# HE280PCB.net
KiCad netlist of a schematic drawn in Altium Designer
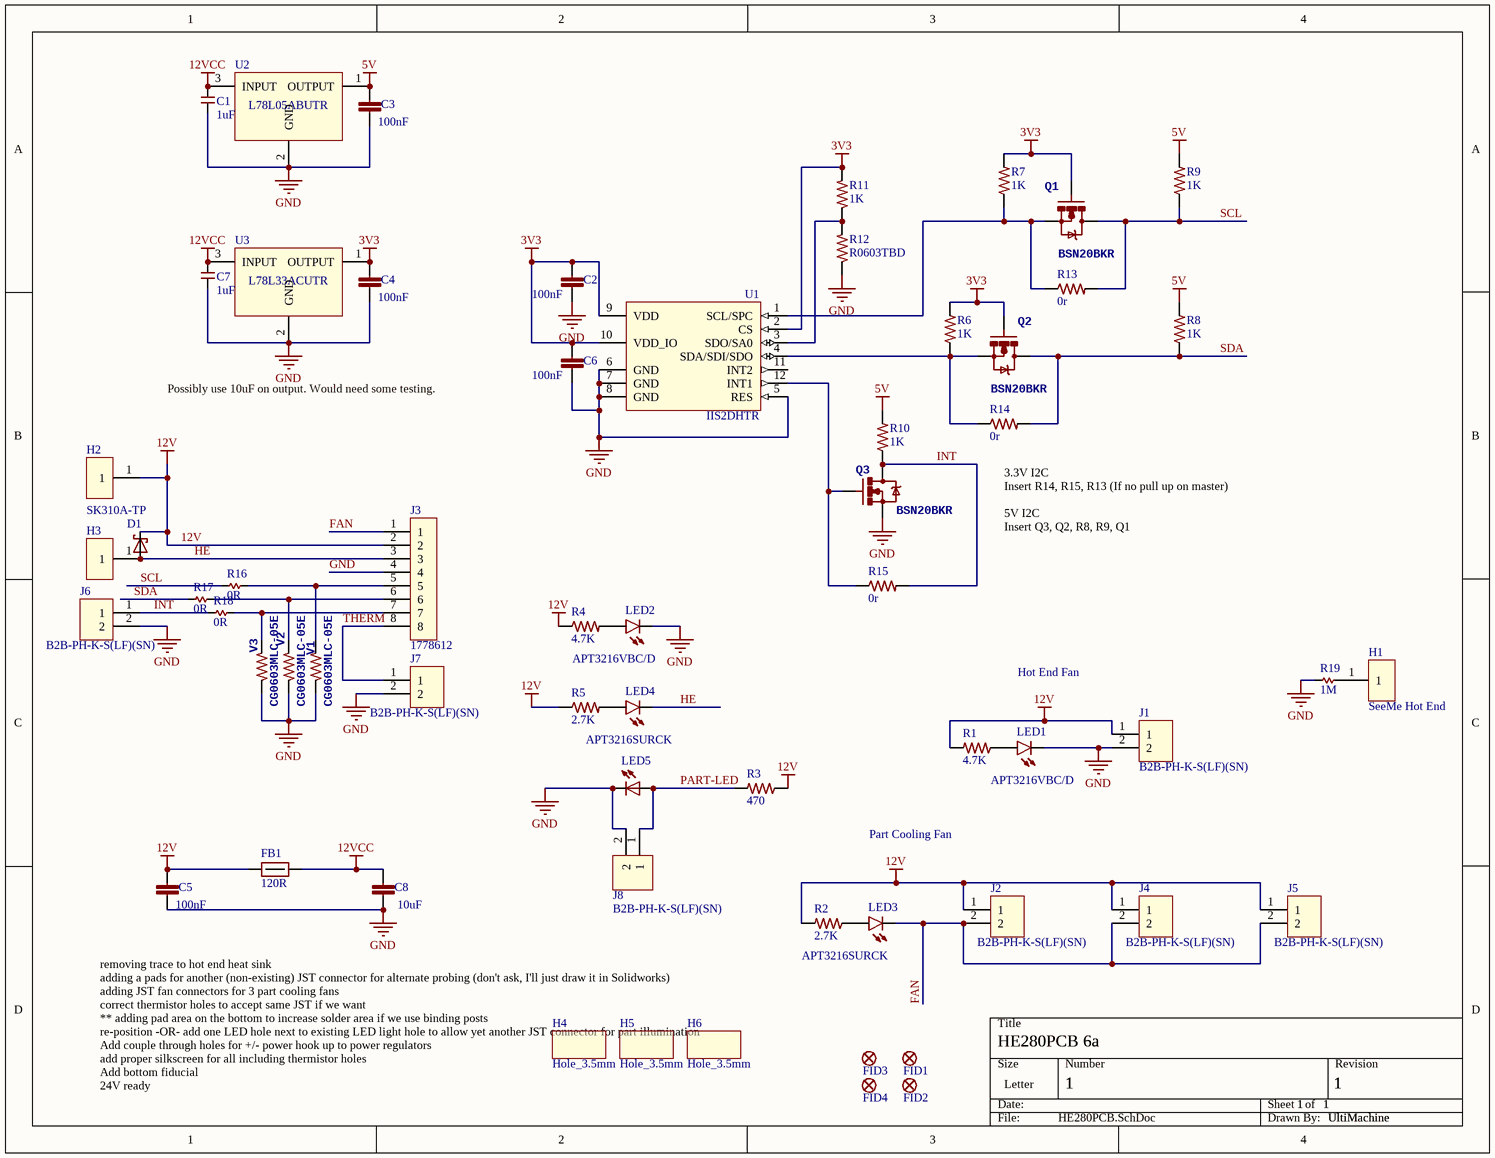
[diagram p0: HE280PCB.SchDoc]

(export (version "E")
  (design (tool "Eeschema 10.0.6"))
  (components
    (comp (ref "C1")
      (value "1uF")
      (footprint "C0805")
      (description "CAP CER 0805 1uF 50V 10% X7R")
      (fields (field (name "MANUFACTURER") "Murata") (field (name "PART") "1uF 50V X7R 0805"))
      (libsource (lib "Capacitors") (part "1uF 0805 50V X7R"))
    )
    (comp (ref "C2")
      (value "100nF")
      (footprint "C0603")
      (description "CAP CER 0603 100nF 50V 10% X7R")
      (fields
        (field (name "MANUFACTURERPARTNUMBER") "C0603C104K5RACTU")
        (field (name "PUBLISHER") "UltiMachine")
      )
      (libsource (lib "") (part "C0603C104K5RACTU_1"))
    )
    (comp (ref "C3")
      (value "100nF")
      (footprint "C0603")
      (description "CAP CER 0603 100nF 50V 10% X7R")
      (fields
        (field (name "MANUFACTURERPARTNUMBER") "C0603C104K5RACTU")
        (field (name "PUBLISHER") "UltiMachine")
      )
      (libsource (lib "3Delight") (part "C0603C104K5RACTU"))
    )
    (comp (ref "C4")
      (value "100nF")
      (footprint "C0603")
      (description "CAP CER 0603 100nF 50V 10% X7R")
      (fields
        (field (name "MANUFACTURERPARTNUMBER") "C0603C104K5RACTU")
        (field (name "PUBLISHER") "UltiMachine")
      )
      (libsource (lib "3Delight") (part "C0603C104K5RACTU"))
    )
    (comp (ref "C5")
      (value "100nF")
      (footprint "C0603")
      (description "CAP CER 0603 100nF 50V 10% X7R")
      (fields
        (field (name "MANUFACTURERPARTNUMBER") "C0603C104K5RACTU")
        (field (name "PUBLISHER") "UltiMachine")
      )
      (libsource (lib "3Delight") (part "C0603C104K5RACTU"))
    )
    (comp (ref "C6")
      (value "100nF")
      (footprint "C0603")
      (description "CAP CER 0603 100nF 50V 10% X7R")
      (fields
        (field (name "MANUFACTURERPARTNUMBER") "C0603C104K5RACTU")
        (field (name "PUBLISHER") "UltiMachine")
      )
      (libsource (lib "") (part "C0603C104K5RACTU_1"))
    )
    (comp (ref "C7")
      (value "1uF")
      (footprint "C0805")
      (description "CAP CER 0805 1uF 50V 10% X7R")
      (fields (field (name "MANUFACTURER") "Murata") (field (name "PART") "1uF 50V X7R 0805"))
      (libsource (lib "Capacitors") (part "1uF 0805 50V X7R"))
    )
    (comp (ref "C8")
      (value "10uF")
      (footprint "C0805")
      (description "CAP CER 10UF 16V X5R 0805")
      (fields
        (field (name "MANUFACTURERPARTNUMBER") "GRM21BR61C106KE15K")
        (field (name "PUBLISHER") "UltiMachine")
      )
      (libsource (lib "3Delight") (part "GRM21BR61C106KE15K"))
    )
    (comp (ref "D1")
      (value "SK310A-TP")
      (footprint "SMA-SM")
      (description "DIODE Schottky 3A SMA")
      (fields (field (name "MANUFACTURERPARTNUMBER") "SK310A") (field (name "PUBLISHER") "UltiMachine"))
      (libsource (lib "3Delight") (part "SK310A"))
    )
    (comp (ref "FB1")
      (value "120R")
      (footprint "R0402")
      (description "FERRITE BEAD 120 OHM 0402 1LN")
      (fields (field (name "MANUFACTURER") "Taiyo Yuden") (field (name "PART") "FERRITE 120R 1A 0402"))
      (libsource (lib "Inductors_1") (part "FERRITE 120R 1A 0402"))
    )
    (comp (ref "FID1")
      (value "FIDUCIAL")
      (footprint "FIDUCIAL-2x3-Panel")
      (description "Fiducial")
      (fields (field (name "PUBLISHER") "UltiMachine"))
      (libsource (lib "3Delight") (part "FIDUCIAL"))
    )
    (comp (ref "FID2")
      (value "FIDUCIAL")
      (footprint "FIDUCIAL-2x3-Panel")
      (description "Fiducial")
      (fields (field (name "PUBLISHER") "UltiMachine"))
      (libsource (lib "3Delight") (part "FIDUCIAL"))
    )
    (comp (ref "FID3")
      (value "FIDUCIAL")
      (footprint "FIDUCIAL-2x3-Panel")
      (description "Fiducial")
      (fields (field (name "PUBLISHER") "UltiMachine"))
      (libsource (lib "3Delight") (part "FIDUCIAL"))
    )
    (comp (ref "FID4")
      (value "FIDUCIAL")
      (footprint "FIDUCIAL-2x3-Panel")
      (description "Fiducial")
      (fields (field (name "PUBLISHER") "UltiMachine"))
      (libsource (lib "3Delight") (part "FIDUCIAL"))
    )
    (comp (ref "H1")
      (value "SeeMe Hot End")
      (footprint "PAD 0.1-HOTEND")
      (libsource (lib "3Delight") (part "SeeMe Hot End"))
    )
    (comp (ref "H2")
      (value "PTH 49mil")
      (footprint "PTH 49mil")
      (libsource (lib "3Delight") (part "PTH 49mil"))
    )
    (comp (ref "H3")
      (value "PTH 49mil")
      (footprint "PTH 49mil")
      (libsource (lib "3Delight") (part "PTH 49mil"))
    )
    (comp (ref "H4")
      (value "Hole_3.5mm")
      (footprint "Hole_3.5mm")
      (libsource (lib "3Delight") (part "Hole_3.5mm"))
    )
    (comp (ref "H5")
      (value "Hole_3.5mm")
      (footprint "Hole_3.5mm")
      (libsource (lib "3Delight") (part "Hole_3.5mm"))
    )
    (comp (ref "H6")
      (value "Hole_3.5mm")
      (footprint "Hole_3.5mm")
      (libsource (lib "3Delight") (part "Hole_3.5mm"))
    )
    (comp (ref "J1")
      (value "B2B-PH-K-S(LF)(SN)")
      (footprint "3Delight:B2B-PH-K-S(LF)(SN)")
      (description "Conn JST 2 position")
      (libsource (lib "") (part "B2B-PH-K-S(LF)(SN)_1"))
    )
    (comp (ref "J2")
      (value "B2B-PH-K-S(LF)(SN)")
      (footprint "3Delight:B2B-PH-K-S(LF)(SN)")
      (description "Conn JST 2 position")
      (libsource (lib "") (part "B2B-PH-K-S(LF)(SN)_1"))
    )
    (comp (ref "J3")
      (value "1778612")
      (footprint "1778612")
      (description "Conn 2.5mm Pin in Paste Phoenix")
      (libsource (lib "3Delight") (part "1778612"))
    )
    (comp (ref "J4")
      (value "B2B-PH-K-S(LF)(SN)")
      (footprint "3Delight:B2B-PH-K-S(LF)(SN)")
      (description "Conn JST 2 position")
      (libsource (lib "") (part "B2B-PH-K-S(LF)(SN)_1"))
    )
    (comp (ref "J5")
      (value "B2B-PH-K-S(LF)(SN)")
      (footprint "3Delight:B2B-PH-K-S(LF)(SN)")
      (description "Conn JST 2 position")
      (libsource (lib "") (part "B2B-PH-K-S(LF)(SN)_1"))
    )
    (comp (ref "J6")
      (value "B2B-PH-K-S(LF)(SN)")
      (footprint "3Delight:B2B-PH-K-S(LF)(SN)")
      (description "Conn JST 2 position")
      (libsource (lib "3Delight") (part "B2B-PH-K-S(LF)(SN)"))
    )
    (comp (ref "J7")
      (value "B2B-PH-K-S(LF)(SN)")
      (footprint "3Delight:B2B-PH-K-S(LF)(SN)")
      (description "Conn JST 2 position")
      (libsource (lib "") (part "B2B-PH-K-S(LF)(SN)_1"))
    )
    (comp (ref "J8")
      (value "B2B-PH-K-S(LF)(SN)")
      (footprint "3Delight:B2B-PH-K-S(LF)(SN)")
      (description "Conn JST 2 position")
      (libsource (lib "3Delight") (part "B2B-PH-K-S(LF)(SN)"))
    )
    (comp (ref "LED1")
      (value "APT3216VBC/D")
      (footprint "LED1206")
      (description "LED BLUE CLEAR 1206 SMD")
      (fields (field (name "PUBLISHER") "UltiMachine"))
      (libsource (lib "3Delight") (part "APT3216VBC/D"))
    )
    (comp (ref "LED2")
      (value "APT3216VBC/D")
      (footprint "LED1206")
      (description "LED BLUE CLEAR 1206 SMD")
      (fields (field (name "PUBLISHER") "UltiMachine"))
      (libsource (lib "3Delight") (part "APT3216VBC/D"))
    )
    (comp (ref "LED3")
      (value "APT3216SURCK")
      (footprint "LED1206")
      (description "LED RED CLEAR 1206 SMD")
      (fields (field (name "PUBLISHER") "UltiMachine"))
      (libsource (lib "3Delight") (part "APT3216SURCK"))
    )
    (comp (ref "LED4")
      (value "APT3216SURCK")
      (footprint "LED1206")
      (description "LED RED CLEAR 1206 SMD")
      (fields (field (name "PUBLISHER") "UltiMachine"))
      (libsource (lib "3Delight") (part "APT3216SURCK"))
    )
    (comp (ref "LED5")
      (value "LED-Hot End")
      (footprint "HE LED")
      (libsource (lib "3Delight") (part "LED-Hot End"))
    )
    (comp (ref "Q1")
      (value "BSN20BKR")
      (footprint "SOT23-3")
      (description "MOSFET N-CH 60V 0.265A SOT-23")
      (fields (field (name "PUBLISHER") "UltiMachine"))
      (libsource (lib "3Delight") (part "BSN20BKR"))
    )
    (comp (ref "Q2")
      (value "BSN20BKR")
      (footprint "SOT23-3")
      (description "MOSFET N-CH 60V 0.265A SOT-23")
      (fields (field (name "PUBLISHER") "UltiMachine"))
      (libsource (lib "3Delight") (part "BSN20BKR"))
    )
    (comp (ref "Q3")
      (value "BSN20BKR")
      (footprint "SOT23-3")
      (description "MOSFET N-CH 60V 0.265A SOT-23")
      (fields (field (name "PUBLISHER") "UltiMachine"))
      (libsource (lib "") (part "BSN20BKR_1"))
    )
    (comp (ref "R1")
      (value "4.7K")
      (footprint "R0805")
      (description "RES SMD 4.7K OHM 5% 1/8W 0805")
      (fields (field (name "PUBLISHER") "UltiMachine"))
      (libsource (lib "3Delight") (part "RC0805FR-074K7L"))
    )
    (comp (ref "R2")
      (value "2.7K")
      (footprint "R0805")
      (description "RES SMD 2.7K OHM 5% 1/8W 0805")
      (fields (field (name "PUBLISHER") "UltiMachine"))
      (libsource (lib "3Delight") (part "RC0805FR-072K7L"))
    )
    (comp (ref "R3")
      (value "470")
      (footprint "R0805")
      (description "RES SMD 470 OHM 5% 1/8W 0805")
      (fields (field (name "PUBLISHER") "UltiMachine"))
      (libsource (lib "3Delight") (part "RC0805JR-07470RL"))
    )
    (comp (ref "R4")
      (value "4.7K")
      (footprint "R0805")
      (description "RES SMD 4.7K OHM 5% 1/8W 0805")
      (fields (field (name "PUBLISHER") "UltiMachine"))
      (libsource (lib "3Delight") (part "RC0805FR-074K7L"))
    )
    (comp (ref "R5")
      (value "2.7K")
      (footprint "R0805")
      (description "RES SMD 2.7K OHM 5% 1/8W 0805")
      (fields (field (name "PUBLISHER") "UltiMachine"))
      (libsource (lib "3Delight") (part "RC0805FR-072K7L"))
    )
    (comp (ref "R6")
      (value "1K")
      (footprint "R0603")
      (description "RES 0603 1K 100mW 1%")
      (fields
        (field (name "MANUFACTURERPARTNUMBER") "ERJ-3EKF1001V")
        (field (name "PUBLISHER") "UltiMachine")
      )
      (libsource (lib "3Delight") (part "ERJ-3EKF1001V"))
    )
    (comp (ref "R7")
      (value "1K")
      (footprint "R0603")
      (description "RES 0603 1K 100mW 1%")
      (fields
        (field (name "MANUFACTURERPARTNUMBER") "ERJ-3EKF1001V")
        (field (name "PUBLISHER") "UltiMachine")
      )
      (libsource (lib "3Delight") (part "ERJ-3EKF1001V"))
    )
    (comp (ref "R8")
      (value "1K")
      (footprint "R0603")
      (description "RES 0603 1K 100mW 1%")
      (fields
        (field (name "MANUFACTURERPARTNUMBER") "ERJ-3EKF1001V")
        (field (name "PUBLISHER") "UltiMachine")
      )
      (libsource (lib "3Delight") (part "ERJ-3EKF1001V"))
    )
    (comp (ref "R9")
      (value "1K")
      (footprint "R0603")
      (description "RES 0603 1K 100mW 1%")
      (fields
        (field (name "MANUFACTURERPARTNUMBER") "ERJ-3EKF1001V")
        (field (name "PUBLISHER") "UltiMachine")
      )
      (libsource (lib "3Delight") (part "ERJ-3EKF1001V"))
    )
    (comp (ref "R10")
      (value "1K")
      (footprint "R0603")
      (description "RES 0603 1K 100mW 1%")
      (fields
        (field (name "MANUFACTURERPARTNUMBER") "ERJ-3EKF1001V")
        (field (name "PUBLISHER") "UltiMachine")
      )
      (libsource (lib "3Delight") (part "ERJ-3EKF1001V"))
    )
    (comp (ref "R11")
      (value "1K")
      (footprint "R0603")
      (description "RES 0603 1K 100mW 1%")
      (fields
        (field (name "MANUFACTURERPARTNUMBER") "ERJ-3EKF1001V")
        (field (name "PUBLISHER") "UltiMachine")
      )
      (libsource (lib "3Delight") (part "ERJ-3EKF1001V"))
    )
    (comp (ref "R12")
      (value "R0603TBD")
      (footprint "R0603")
      (description "Resistor")
      (fields (field (name "PUBLISHER") "UltiMachine"))
      (libsource (lib "3Delight") (part "R0603TBD"))
    )
    (comp (ref "R13")
      (value "0r")
      (footprint "R0603")
      (description "RES 0603 0r 100mW 1%")
      (fields
        (field (name "MANUFACTURERPARTNUMBER") "CR0603J000ELF")
        (field (name "PUBLISHER") "UltiMachine")
      )
      (libsource (lib "3Delight") (part "CR0603J000ELF"))
    )
    (comp (ref "R14")
      (value "0r")
      (footprint "R0603")
      (description "RES 0603 0r 100mW 1%")
      (fields
        (field (name "MANUFACTURERPARTNUMBER") "CR0603J000ELF")
        (field (name "PUBLISHER") "UltiMachine")
      )
      (libsource (lib "3Delight") (part "CR0603J000ELF"))
    )
    (comp (ref "R15")
      (value "0r")
      (footprint "R0603")
      (description "RES 0603 0r 100mW 1%")
      (fields
        (field (name "MANUFACTURERPARTNUMBER") "CR0603J000ELF")
        (field (name "PUBLISHER") "UltiMachine")
      )
      (libsource (lib "3Delight") (part "CR0603J000ELF"))
    )
    (comp (ref "R16")
      (value "0R")
      (footprint "R0402")
      (description "RES SMD 0.0OHM JUMPER 1/10W 0402")
      (fields (field (name "MANUFACTURER") "Panasonic") (field (name "TOLERANCE") "1%"))
      (libsource (lib "Resistors") (part "0R 0402"))
    )
    (comp (ref "R17")
      (value "0R")
      (footprint "R0402")
      (description "RES SMD 0.0OHM JUMPER 1/10W 0402")
      (fields (field (name "MANUFACTURER") "Panasonic") (field (name "TOLERANCE") "1%"))
      (libsource (lib "Resistors") (part "0R 0402"))
    )
    (comp (ref "R18")
      (value "0R")
      (footprint "R0402")
      (description "RES SMD 0.0OHM JUMPER 1/10W 0402")
      (fields (field (name "MANUFACTURER") "Panasonic") (field (name "TOLERANCE") "1%"))
      (libsource (lib "Resistors") (part "0R 0402"))
    )
    (comp (ref "R19")
      (value "1M")
      (footprint "3Delight:R0402")
      (description "RES 0402 1M 100mW 5%")
      (fields (field (name "MANUFACTURER") "Panasonic") (field (name "PART") "1M 5% 0402"))
      (libsource (lib "Resistors") (part "1M 5% 0402"))
    )
    (comp (ref "U1")
      (value "IIS2DHTR")
      (footprint "LGA12C50P4X4_200X200X100")
      (description "3-axis accelerometer with digital output")
      (libsource (lib "3Delight") (part "IIS2DHTR"))
    )
    (comp (ref "U2")
      (value "L78L05ABUTR")
      (footprint "SOT89-150P347X160-3L")
      (description "IC REG LDO 5V 0.1A SOT89-3")
      (libsource (lib "3Delight") (part "L78L05ABUTR"))
    )
    (comp (ref "U3")
      (value "L78L33ACUTR")
      (footprint "SOT89-150P347X160-3L")
      (description "IC REG LDO 3.3V 0.1A SOT89-3")
      (libsource (lib "3Delight") (part "L78L33ACUTR"))
    )
    (comp (ref "V1")
      (value "CG0603MLC-05E")
      (footprint "R0603")
      (description "RESISTOR, American symbol")
      (libsource (lib "resistor") (part "R-US_R0603"))
    )
    (comp (ref "V2")
      (value "CG0603MLC-05E")
      (footprint "R0603")
      (description "RESISTOR, American symbol")
      (libsource (lib "resistor") (part "R-US_R0603"))
    )
    (comp (ref "V3")
      (value "CG0603MLC-05E")
      (footprint "R0603")
      (description "RESISTOR, American symbol")
      (libsource (lib "resistor") (part "R-US_R0603"))
    )
  )
  (nets
    (net (code "1") (name "/FAN") (class "Default")
      (node (ref "J2") (pin "2") (pinfunction "2_2") (pintype "passive"))
      (node (ref "J3") (pin "1") (pinfunction "1_1") (pintype "passive"))
      (node (ref "J4") (pin "2") (pinfunction "2_2") (pintype "passive"))
      (node (ref "J5") (pin "2") (pinfunction "2_2") (pintype "passive"))
      (node (ref "LED3") (pin "C") (pinfunction "C_C") (pintype "passive"))
    )
    (net (code "2") (name "/HE") (class "Default")
      (node (ref "D1") (pin "A") (pinfunction "A_A") (pintype "passive"))
      (node (ref "H3") (pin "1") (pinfunction "1_1") (pintype "passive"))
      (node (ref "J3") (pin "3") (pinfunction "3_3") (pintype "passive"))
      (node (ref "LED4") (pin "C") (pinfunction "C_C") (pintype "passive"))
    )
    (net (code "3") (name "/INT") (class "Default")
      (node (ref "J6") (pin "1") (pinfunction "1_1") (pintype "passive"))
      (node (ref "Q3") (pin "3") (pinfunction "D_3") (pintype "passive"))
      (node (ref "R10") (pin "1") (pinfunction "1_1") (pintype "passive"))
      (node (ref "R15") (pin "2") (pinfunction "2_2") (pintype "passive"))
      (node (ref "R18") (pin "1") (pinfunction "1_1") (pintype "passive"))
    )
    (net (code "4") (name "/PART-LED") (class "Default")
      (node (ref "J8") (pin "1") (pinfunction "1_1") (pintype "passive"))
      (node (ref "LED5") (pin "A") (pinfunction "A_A") (pintype "passive"))
      (node (ref "R3") (pin "2") (pinfunction "2_2") (pintype "passive"))
    )
    (net (code "5") (name "/SCL") (class "Default")
      (node (ref "Q1") (pin "3") (pinfunction "D_3") (pintype "passive"))
      (node (ref "R13") (pin "2") (pinfunction "2_2") (pintype "passive"))
      (node (ref "R16") (pin "1") (pinfunction "1_1") (pintype "passive"))
      (node (ref "R9") (pin "1") (pinfunction "1_1") (pintype "passive"))
    )
    (net (code "6") (name "/SDA") (class "Default")
      (node (ref "Q2") (pin "3") (pinfunction "D_3") (pintype "passive"))
      (node (ref "R14") (pin "2") (pinfunction "2_2") (pintype "passive"))
      (node (ref "R17") (pin "1") (pinfunction "1_1") (pintype "passive"))
      (node (ref "R8") (pin "1") (pinfunction "1_1") (pintype "passive"))
    )
    (net (code "7") (name "/THERM") (class "Default")
      (node (ref "J3") (pin "8") (pinfunction "8_8") (pintype "passive"))
      (node (ref "J7") (pin "1") (pinfunction "1_1") (pintype "passive"))
    )
    (net (code "8") (name "3V3") (class "Default")
      (node (ref "C2") (pin "1") (pinfunction "1_1") (pintype "passive"))
      (node (ref "C4") (pin "1") (pinfunction "1_1") (pintype "passive"))
      (node (ref "C6") (pin "1") (pinfunction "1_1") (pintype "passive"))
      (node (ref "Q1") (pin "1") (pinfunction "G_1") (pintype "passive"))
      (node (ref "Q2") (pin "1") (pinfunction "G_1") (pintype "passive"))
      (node (ref "R11") (pin "2") (pinfunction "2_2") (pintype "passive"))
      (node (ref "R6") (pin "2") (pinfunction "2_2") (pintype "passive"))
      (node (ref "R7") (pin "2") (pinfunction "2_2") (pintype "passive"))
      (node (ref "U1") (pin "10") (pinfunction "VDD_IO_10") (pintype "power_in"))
      (node (ref "U1") (pin "2") (pinfunction "CS_2") (pintype "input"))
      (node (ref "U1") (pin "9") (pinfunction "VDD_9") (pintype "power_in"))
      (node (ref "U3") (pin "1") (pinfunction "OUTPUT_1") (pintype "power_in"))
    )
    (net (code "9") (name "5V") (class "Default")
      (node (ref "C3") (pin "1") (pinfunction "1_1") (pintype "passive"))
      (node (ref "R10") (pin "2") (pinfunction "2_2") (pintype "passive"))
      (node (ref "R8") (pin "2") (pinfunction "2_2") (pintype "passive"))
      (node (ref "R9") (pin "2") (pinfunction "2_2") (pintype "passive"))
      (node (ref "U2") (pin "1") (pinfunction "OUTPUT_1") (pintype "power_in"))
    )
    (net (code "10") (name "12V") (class "Default")
      (node (ref "C5") (pin "1") (pinfunction "1_1") (pintype "passive"))
      (node (ref "D1") (pin "C") (pinfunction "C_C") (pintype "passive"))
      (node (ref "FB1") (pin "1") (pinfunction "1_1") (pintype "passive"))
      (node (ref "H2") (pin "1") (pinfunction "1_1") (pintype "passive"))
      (node (ref "J1") (pin "1") (pinfunction "1_1") (pintype "passive"))
      (node (ref "J2") (pin "1") (pinfunction "1_1") (pintype "passive"))
      (node (ref "J3") (pin "2") (pinfunction "2_2") (pintype "passive"))
      (node (ref "J4") (pin "1") (pinfunction "1_1") (pintype "passive"))
      (node (ref "J5") (pin "1") (pinfunction "1_1") (pintype "passive"))
      (node (ref "R1") (pin "2") (pinfunction "2_2") (pintype "passive"))
      (node (ref "R2") (pin "2") (pinfunction "2_2") (pintype "passive"))
      (node (ref "R3") (pin "1") (pinfunction "1_1") (pintype "passive"))
      (node (ref "R4") (pin "1") (pinfunction "1_1") (pintype "passive"))
      (node (ref "R5") (pin "1") (pinfunction "1_1") (pintype "passive"))
    )
    (net (code "11") (name "12VCC") (class "Default")
      (node (ref "C1") (pin "1") (pinfunction "1_1") (pintype "passive"))
      (node (ref "C7") (pin "1") (pinfunction "1_1") (pintype "passive"))
      (node (ref "C8") (pin "1") (pinfunction "1_1") (pintype "passive"))
      (node (ref "FB1") (pin "2") (pinfunction "2_2") (pintype "passive"))
      (node (ref "U2") (pin "3") (pinfunction "INPUT_3") (pintype "power_in"))
      (node (ref "U3") (pin "3") (pinfunction "INPUT_3") (pintype "power_in"))
    )
    (net (code "12") (name "GND") (class "Default")
      (node (ref "C1") (pin "2") (pinfunction "2_2") (pintype "passive"))
      (node (ref "C2") (pin "2") (pinfunction "2_2") (pintype "passive"))
      (node (ref "C3") (pin "2") (pinfunction "2_2") (pintype "passive"))
      (node (ref "C4") (pin "2") (pinfunction "2_2") (pintype "passive"))
      (node (ref "C5") (pin "2") (pinfunction "2_2") (pintype "passive"))
      (node (ref "C6") (pin "2") (pinfunction "2_2") (pintype "passive"))
      (node (ref "C7") (pin "2") (pinfunction "2_2") (pintype "passive"))
      (node (ref "C8") (pin "2") (pinfunction "2_2") (pintype "passive"))
      (node (ref "J1") (pin "2") (pinfunction "2_2") (pintype "passive"))
      (node (ref "J3") (pin "4") (pinfunction "4_4") (pintype "passive"))
      (node (ref "J6") (pin "2") (pinfunction "2_2") (pintype "passive"))
      (node (ref "J7") (pin "2") (pinfunction "2_2") (pintype "passive"))
      (node (ref "J8") (pin "2") (pinfunction "2_2") (pintype "passive"))
      (node (ref "LED1") (pin "C") (pinfunction "C_C") (pintype "passive"))
      (node (ref "LED2") (pin "C") (pinfunction "C_C") (pintype "passive"))
      (node (ref "LED5") (pin "C") (pinfunction "C_C") (pintype "passive"))
      (node (ref "Q3") (pin "2") (pinfunction "S_2") (pintype "passive"))
      (node (ref "R12") (pin "1") (pinfunction "1_1") (pintype "passive"))
      (node (ref "R19") (pin "1") (pinfunction "1_1") (pintype "passive"))
      (node (ref "U1") (pin "5") (pinfunction "RES_5") (pintype "input"))
      (node (ref "U1") (pin "6") (pinfunction "GND_6") (pintype "power_in"))
      (node (ref "U1") (pin "7") (pinfunction "GND_7") (pintype "power_in"))
      (node (ref "U1") (pin "8") (pinfunction "GND_8") (pintype "power_in"))
      (node (ref "U2") (pin "2") (pinfunction "GND_2") (pintype "power_in"))
      (node (ref "U3") (pin "2") (pinfunction "GND_2") (pintype "power_in"))
      (node (ref "V1") (pin "1") (pinfunction "1_1") (pintype "passive"))
      (node (ref "V2") (pin "1") (pinfunction "1_1") (pintype "passive"))
      (node (ref "V3") (pin "1") (pinfunction "1_1") (pintype "passive"))
    )
    (net (code "13") (name "Net-(H1-Pad1)") (class "Default")
      (node (ref "H1") (pin "1") (pinfunction "1_1") (pintype "passive"))
      (node (ref "R19") (pin "2") (pinfunction "2_2") (pintype "passive"))
    )
    (net (code "14") (name "Net-(J3-Pad5)") (class "Default")
      (node (ref "J3") (pin "5") (pinfunction "5_5") (pintype "passive"))
      (node (ref "R16") (pin "2") (pinfunction "2_2") (pintype "passive"))
      (node (ref "V1") (pin "2") (pinfunction "2_2") (pintype "passive"))
    )
    (net (code "15") (name "Net-(J3-Pad6)") (class "Default")
      (node (ref "J3") (pin "6") (pinfunction "6_6") (pintype "passive"))
      (node (ref "R17") (pin "2") (pinfunction "2_2") (pintype "passive"))
      (node (ref "V2") (pin "2") (pinfunction "2_2") (pintype "passive"))
    )
    (net (code "16") (name "Net-(J3-Pad7)") (class "Default")
      (node (ref "J3") (pin "7") (pinfunction "7_7") (pintype "passive"))
      (node (ref "R18") (pin "2") (pinfunction "2_2") (pintype "passive"))
      (node (ref "V3") (pin "2") (pinfunction "2_2") (pintype "passive"))
    )
    (net (code "17") (name "Net-(LED1-PadA)") (class "Default")
      (node (ref "LED1") (pin "A") (pinfunction "A_A") (pintype "passive"))
      (node (ref "R1") (pin "1") (pinfunction "1_1") (pintype "passive"))
    )
    (net (code "18") (name "Net-(LED2-PadA)") (class "Default")
      (node (ref "LED2") (pin "A") (pinfunction "A_A") (pintype "passive"))
      (node (ref "R4") (pin "2") (pinfunction "2_2") (pintype "passive"))
    )
    (net (code "19") (name "Net-(LED3-PadA)") (class "Default")
      (node (ref "LED3") (pin "A") (pinfunction "A_A") (pintype "passive"))
      (node (ref "R2") (pin "1") (pinfunction "1_1") (pintype "passive"))
    )
    (net (code "20") (name "Net-(LED4-PadA)") (class "Default")
      (node (ref "LED4") (pin "A") (pinfunction "A_A") (pintype "passive"))
      (node (ref "R5") (pin "2") (pinfunction "2_2") (pintype "passive"))
    )
    (net (code "21") (name "Net-(Q1-S)") (class "Default")
      (node (ref "Q1") (pin "2") (pinfunction "S_2") (pintype "passive"))
      (node (ref "R13") (pin "1") (pinfunction "1_1") (pintype "passive"))
      (node (ref "R7") (pin "1") (pinfunction "1_1") (pintype "passive"))
      (node (ref "U1") (pin "1") (pinfunction "SCL/SPC_1") (pintype "input"))
    )
    (net (code "22") (name "Net-(Q2-S)") (class "Default")
      (node (ref "Q2") (pin "2") (pinfunction "S_2") (pintype "passive"))
      (node (ref "R14") (pin "1") (pinfunction "1_1") (pintype "passive"))
      (node (ref "R6") (pin "1") (pinfunction "1_1") (pintype "passive"))
      (node (ref "U1") (pin "4") (pinfunction "SDA/SDI/SDO_4") (pintype "bidirectional"))
    )
    (net (code "23") (name "Net-(Q3-G)") (class "Default")
      (node (ref "Q3") (pin "1") (pinfunction "G_1") (pintype "passive"))
      (node (ref "R15") (pin "1") (pinfunction "1_1") (pintype "passive"))
      (node (ref "U1") (pin "12") (pinfunction "INT1_12") (pintype "output"))
    )
    (net (code "24") (name "Net-(U1-SDO{slash}SA0)") (class "Default")
      (node (ref "R11") (pin "1") (pinfunction "1_1") (pintype "passive"))
      (node (ref "R12") (pin "2") (pinfunction "2_2") (pintype "passive"))
      (node (ref "U1") (pin "3") (pinfunction "SDO/SA0_3") (pintype "bidirectional"))
    )
    (net (code "25") (name "unconnected-(U1-INT2-Pad11)") (class "Default")
      (node (ref "U1") (pin "11") (pinfunction "INT2_11") (pintype "output"))
    )
  )
)
